# microverb.net
KiCad netlist of a schematic drawn in EAGLE
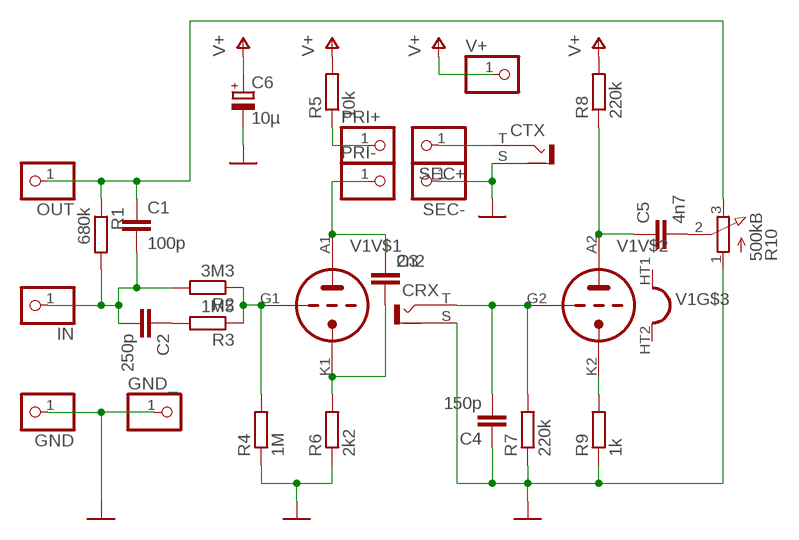
[diagram p0: schematic, sheet 1]

(export (version "E")
  (design (tool "Eeschema 10.0.6"))
  (components
    (comp (ref "C1")
      (value "100p")
      (footprint "eagle-import:C1206")
      (libsource (lib "eagle-import") (part "C-EUC1206"))
    )
    (comp (ref "C2")
      (value "250p")
      (footprint "eagle-import:C1206")
      (libsource (lib "eagle-import") (part "C-EUC1206"))
    )
    (comp (ref "C3")
      (value "2n2")
      (footprint "eagle-import:C1206")
      (libsource (lib "eagle-import") (part "C-EUC1206"))
    )
    (comp (ref "C4")
      (value "150p")
      (footprint "eagle-import:C1206")
      (libsource (lib "eagle-import") (part "C-EUC1206"))
    )
    (comp (ref "C5")
      (value "4n7")
      (footprint "eagle-import:C1206")
      (libsource (lib "eagle-import") (part "C-EUC1206"))
    )
    (comp (ref "C6")
      (value "10µ")
      (footprint "eagle-import:E5-10,5")
      (libsource (lib "eagle-import") (part "CPOL-EUE5-10.5"))
    )
    (comp (ref "CRX")
      (value "BTOR1")
      (footprint "eagle-import:BTOR1")
      (fields (field (name "MPN") "BTOR 1"))
      (libsource (lib "eagle-import") (part "BTOR1"))
    )
    (comp (ref "CTX")
      (value "BTOR1")
      (footprint "eagle-import:BTOR1")
      (fields (field (name "MPN") "BTOR 1"))
      (libsource (lib "eagle-import") (part "BTOR1"))
    )
    (comp (ref "GND")
      (value "PINHD-1X1")
      (footprint "eagle-import:1X01")
      (libsource (lib "eagle-import") (part "PINHD-1X1"))
    )
    (comp (ref "GND_")
      (value "PINHD-1X1")
      (footprint "eagle-import:1X01")
      (libsource (lib "eagle-import") (part "PINHD-1X1"))
    )
    (comp (ref "IN")
      (value "PINHD-1X1")
      (footprint "eagle-import:1X01")
      (libsource (lib "eagle-import") (part "PINHD-1X1"))
    )
    (comp (ref "OUT")
      (value "PINHD-1X1")
      (footprint "eagle-import:1X01")
      (libsource (lib "eagle-import") (part "PINHD-1X1"))
    )
    (comp (ref "PRI+")
      (value "PINHD-1X1")
      (footprint "eagle-import:1X01")
      (libsource (lib "eagle-import") (part "PINHD-1X1"))
    )
    (comp (ref "PRI-")
      (value "PINHD-1X1")
      (footprint "eagle-import:1X01")
      (libsource (lib "eagle-import") (part "PINHD-1X1"))
    )
    (comp (ref "R1")
      (value "680k")
      (footprint "eagle-import:R1206")
      (libsource (lib "eagle-import") (part "R-EU_R1206"))
    )
    (comp (ref "R2")
      (value "3M3")
      (footprint "eagle-import:R1206")
      (libsource (lib "eagle-import") (part "R-EU_R1206"))
    )
    (comp (ref "R3")
      (value "1M5")
      (footprint "eagle-import:R1206")
      (libsource (lib "eagle-import") (part "R-EU_R1206"))
    )
    (comp (ref "R4")
      (value "1M")
      (footprint "eagle-import:R1206")
      (libsource (lib "eagle-import") (part "R-EU_R1206"))
    )
    (comp (ref "R5")
      (value "10k")
      (footprint "eagle-import:R2512")
      (libsource (lib "eagle-import") (part "R-EU_R2512"))
    )
    (comp (ref "R6")
      (value "2k2")
      (footprint "eagle-import:R1206")
      (libsource (lib "eagle-import") (part "R-EU_R1206"))
    )
    (comp (ref "R7")
      (value "220k")
      (footprint "eagle-import:R1206")
      (libsource (lib "eagle-import") (part "R-EU_R1206"))
    )
    (comp (ref "R8")
      (value "220k")
      (footprint "eagle-import:R1206")
      (libsource (lib "eagle-import") (part "R-EU_R1206"))
    )
    (comp (ref "R9")
      (value "1k")
      (footprint "eagle-import:R1206")
      (libsource (lib "eagle-import") (part "R-EU_R1206"))
    )
    (comp (ref "R10")
      (value "500kB")
      (footprint "eagle-import:3RP_1610N")
      (libsource (lib "eagle-import") (part "3RP/1610N"))
    )
    (comp (ref "SEC+")
      (value "PINHD-1X1")
      (footprint "eagle-import:1X01")
      (libsource (lib "eagle-import") (part "PINHD-1X1"))
    )
    (comp (ref "SEC-")
      (value "PINHD-1X1")
      (footprint "eagle-import:1X01")
      (libsource (lib "eagle-import") (part "PINHD-1X1"))
    )
    (comp (ref "V+")
      (value "PINHD-1X1")
      (footprint "eagle-import:1X01")
      (libsource (lib "eagle-import") (part "PINHD-1X1"))
    )
    (comp (ref "V1")
      (value "6NXX-PIT")
      (footprint "eagle-import:6NXX-PIT")
      (libsource (lib "eagle-import") (part "6NXX-PIT"))
    )
  )
  (nets
    (net (code "1") (name "GND") (class "Default")
      (node (ref "C4") (pin "1") (pinfunction "1_1") (pintype "passive"))
      (node (ref "C6") (pin "-") (pinfunction "-_-") (pintype "passive"))
      (node (ref "CRX") (pin "S") (pinfunction "2_S") (pintype "passive"))
      (node (ref "CTX") (pin "S") (pinfunction "2_S") (pintype "passive"))
      (node (ref "GND") (pin "1") (pinfunction "1_1") (pintype "passive"))
      (node (ref "GND_") (pin "1") (pinfunction "1_1") (pintype "passive"))
      (node (ref "R10") (pin "1") (pinfunction "A_1") (pintype "passive"))
      (node (ref "R4") (pin "1") (pinfunction "1_1") (pintype "passive"))
      (node (ref "R6") (pin "1") (pinfunction "1_1") (pintype "passive"))
      (node (ref "R7") (pin "1") (pinfunction "1_1") (pintype "passive"))
      (node (ref "R9") (pin "1") (pinfunction "1_1") (pintype "passive"))
      (node (ref "SEC-") (pin "1") (pinfunction "1_1") (pintype "passive"))
    )
    (net (code "2") (name "Net-(C1-Pad2)") (class "Default")
      (node (ref "C1") (pin "2") (pinfunction "2_2") (pintype "passive"))
      (node (ref "C2") (pin "2") (pinfunction "2_2") (pintype "passive"))
      (node (ref "IN") (pin "1") (pinfunction "1_1") (pintype "passive"))
      (node (ref "R1") (pin "2") (pinfunction "2_2") (pintype "passive"))
      (node (ref "R2") (pin "2") (pinfunction "2_2") (pintype "passive"))
    )
    (net (code "3") (name "Net-(C2-Pad1)") (class "Default")
      (node (ref "C2") (pin "1") (pinfunction "1_1") (pintype "passive"))
      (node (ref "R3") (pin "2") (pinfunction "2_2") (pintype "passive"))
    )
    (net (code "4") (name "Net-(CRX-1)") (class "Default")
      (node (ref "C4") (pin "2") (pinfunction "2_2") (pintype "passive"))
      (node (ref "CRX") (pin "T") (pinfunction "1_T") (pintype "passive"))
      (node (ref "R7") (pin "2") (pinfunction "2_2") (pintype "passive"))
      (node (ref "V1") (pin "G2") (pinfunction "TG_G2") (pintype "passive"))
    )
    (net (code "5") (name "Net-(CTX-1)") (class "Default")
      (node (ref "CTX") (pin "T") (pinfunction "1_T") (pintype "passive"))
      (node (ref "SEC+") (pin "1") (pinfunction "1_1") (pintype "passive"))
    )
    (net (code "6") (name "Net-(PRI+-Pad1)") (class "Default")
      (node (ref "PRI+") (pin "1") (pinfunction "1_1") (pintype "passive"))
      (node (ref "R5") (pin "1") (pinfunction "1_1") (pintype "passive"))
    )
    (net (code "7") (name "Net-(R10-E)") (class "Default")
      (node (ref "C1") (pin "1") (pinfunction "1_1") (pintype "passive"))
      (node (ref "OUT") (pin "1") (pinfunction "1_1") (pintype "passive"))
      (node (ref "R1") (pin "1") (pinfunction "1_1") (pintype "passive"))
      (node (ref "R10") (pin "3") (pinfunction "E_3") (pintype "passive"))
    )
    (net (code "8") (name "Net-(R10-S)") (class "Default")
      (node (ref "C5") (pin "2") (pinfunction "2_2") (pintype "passive"))
      (node (ref "R10") (pin "2") (pinfunction "S_2") (pintype "passive"))
    )
    (net (code "9") (name "Net-(V1B-TA)") (class "Default")
      (node (ref "C3") (pin "1") (pinfunction "1_1") (pintype "passive"))
      (node (ref "PRI-") (pin "1") (pinfunction "1_1") (pintype "passive"))
      (node (ref "V1") (pin "A1") (pinfunction "TA_A1") (pintype "passive"))
    )
    (net (code "10") (name "Net-(V1B-TG)") (class "Default")
      (node (ref "R2") (pin "1") (pinfunction "1_1") (pintype "passive"))
      (node (ref "R3") (pin "1") (pinfunction "1_1") (pintype "passive"))
      (node (ref "R4") (pin "2") (pinfunction "2_2") (pintype "passive"))
      (node (ref "V1") (pin "G1") (pinfunction "TG_G1") (pintype "passive"))
    )
    (net (code "11") (name "Net-(V1B-TK)") (class "Default")
      (node (ref "C3") (pin "2") (pinfunction "2_2") (pintype "passive"))
      (node (ref "R6") (pin "2") (pinfunction "2_2") (pintype "passive"))
      (node (ref "V1") (pin "K1") (pinfunction "TK_K1") (pintype "passive"))
    )
    (net (code "12") (name "Net-(V1C-TA)") (class "Default")
      (node (ref "C5") (pin "1") (pinfunction "1_1") (pintype "passive"))
      (node (ref "R8") (pin "1") (pinfunction "1_1") (pintype "passive"))
      (node (ref "V1") (pin "A2") (pinfunction "TA_A2") (pintype "passive"))
    )
    (net (code "13") (name "Net-(V1C-TK)") (class "Default")
      (node (ref "R9") (pin "2") (pinfunction "2_2") (pintype "passive"))
      (node (ref "V1") (pin "K2") (pinfunction "TK_K2") (pintype "passive"))
    )
    (net (code "14") (name "V+") (class "Default")
      (node (ref "C6") (pin "+") (pinfunction "+_+") (pintype "passive"))
      (node (ref "R5") (pin "2") (pinfunction "2_2") (pintype "passive"))
      (node (ref "R8") (pin "2") (pinfunction "2_2") (pintype "passive"))
      (node (ref "V+") (pin "1") (pinfunction "1_1") (pintype "passive"))
    )
    (net (code "15") (name "unconnected-(CRX-2-PadS@1)") (class "Default")
      (node (ref "CRX") (pin "S@1") (pinfunction "2_S@1") (pintype "passive"))
    )
    (net (code "16") (name "unconnected-(CRX-2-PadS@2)") (class "Default")
      (node (ref "CRX") (pin "S@2") (pinfunction "2_S@2") (pintype "passive"))
    )
    (net (code "17") (name "unconnected-(CRX-2-PadS@3)") (class "Default")
      (node (ref "CRX") (pin "S@3") (pinfunction "2_S@3") (pintype "passive"))
    )
    (net (code "18") (name "unconnected-(CTX-2-PadS@1)") (class "Default")
      (node (ref "CTX") (pin "S@1") (pinfunction "2_S@1") (pintype "passive"))
    )
    (net (code "19") (name "unconnected-(CTX-2-PadS@2)") (class "Default")
      (node (ref "CTX") (pin "S@2") (pinfunction "2_S@2") (pintype "passive"))
    )
    (net (code "20") (name "unconnected-(CTX-2-PadS@3)") (class "Default")
      (node (ref "CTX") (pin "S@3") (pinfunction "2_S@3") (pintype "passive"))
    )
    (net (code "21") (name "unconnected-(V1A-H1-PadHT1)") (class "Default")
      (node (ref "V1") (pin "HT1") (pinfunction "H1_HT1") (pintype "passive"))
    )
    (net (code "22") (name "unconnected-(V1A-H2-PadHT2)") (class "Default")
      (node (ref "V1") (pin "HT2") (pinfunction "H2_HT2") (pintype "passive"))
    )
  )
)
